# power_and_interface.net
KiCad netlist of a schematic drawn in Altium Designer
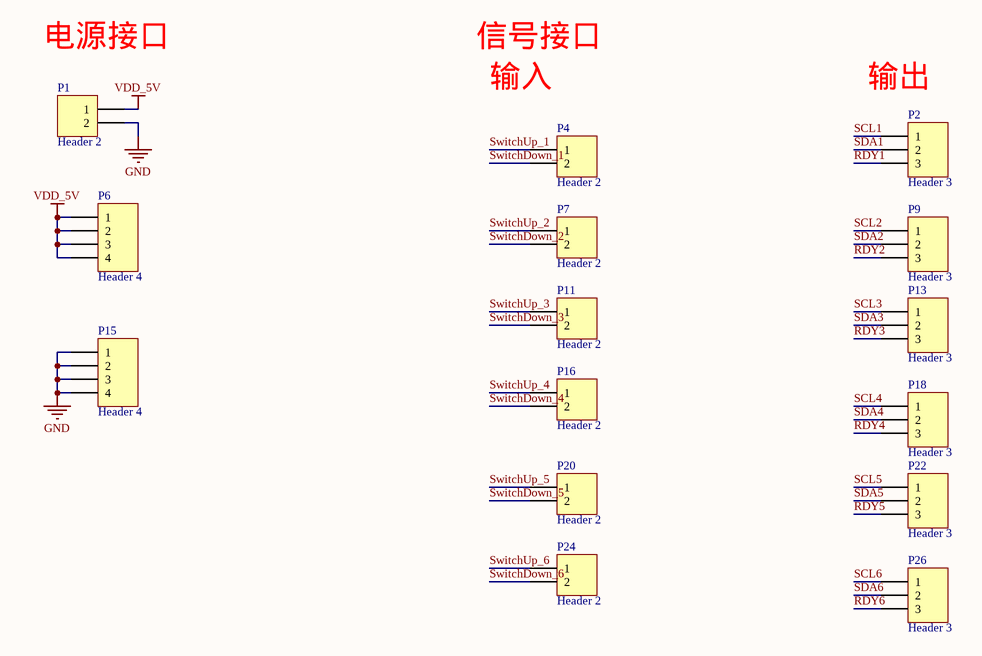
[diagram p0: power_and_interface.SchDoc]

(export (version "E")
  (design (tool "Eeschema 10.0.6"))
  (components
    (comp (ref "P1")
      (value "Header 2")
      (footprint "XH2.54-LI-2P")
      (description "Header, 2-Pin")
      (fields (field (name "PUBLISHER") "Altium Limited"))
      (libsource (lib "") (part "Header 2_1"))
    )
    (comp (ref "P2")
      (value "Header 3")
      (footprint "XH2.0_3p")
      (description "Header, 3-Pin")
      (fields (field (name "PUBLISHER") "Altium Limited"))
      (libsource (lib "Miscellaneous Connectors") (part "Header 3"))
    )
    (comp (ref "P4")
      (value "Header 2")
      (footprint "XH2.0_2p")
      (description "Header, 2-Pin")
      (fields (field (name "PUBLISHER") "Altium Limited"))
      (libsource (lib "Miscellaneous Connectors") (part "Header 2"))
    )
    (comp (ref "P6")
      (value "Header 4")
      (footprint "HDR1X4")
      (description "Header, 4-Pin")
      (fields (field (name "PUBLISHER") "Altium Limited"))
      (libsource (lib "YD-LibrarySCH") (part "Header 4"))
    )
    (comp (ref "P7")
      (value "Header 2")
      (footprint "XH2.0_2p")
      (description "Header, 2-Pin")
      (fields (field (name "PUBLISHER") "Altium Limited"))
      (libsource (lib "Miscellaneous Connectors") (part "Header 2"))
    )
    (comp (ref "P9")
      (value "Header 3")
      (footprint "XH2.0_3p")
      (description "Header, 3-Pin")
      (fields (field (name "PUBLISHER") "Altium Limited"))
      (libsource (lib "Miscellaneous Connectors") (part "Header 3"))
    )
    (comp (ref "P11")
      (value "Header 2")
      (footprint "XH2.0_2p")
      (description "Header, 2-Pin")
      (fields (field (name "PUBLISHER") "Altium Limited"))
      (libsource (lib "Miscellaneous Connectors") (part "Header 2"))
    )
    (comp (ref "P13")
      (value "Header 3")
      (footprint "XH2.0_3p")
      (description "Header, 3-Pin")
      (fields (field (name "PUBLISHER") "Altium Limited"))
      (libsource (lib "Miscellaneous Connectors") (part "Header 3"))
    )
    (comp (ref "P15")
      (value "Header 4")
      (footprint "HDR1X4")
      (description "Header, 4-Pin")
      (fields (field (name "PUBLISHER") "Altium Limited"))
      (libsource (lib "YD-LibrarySCH") (part "Header 4"))
    )
    (comp (ref "P16")
      (value "Header 2")
      (footprint "XH2.0_2p")
      (description "Header, 2-Pin")
      (fields (field (name "PUBLISHER") "Altium Limited"))
      (libsource (lib "Miscellaneous Connectors") (part "Header 2"))
    )
    (comp (ref "P18")
      (value "Header 3")
      (footprint "XH2.0_3p")
      (description "Header, 3-Pin")
      (fields (field (name "PUBLISHER") "Altium Limited"))
      (libsource (lib "Miscellaneous Connectors") (part "Header 3"))
    )
    (comp (ref "P20")
      (value "Header 2")
      (footprint "XH2.0_2p")
      (description "Header, 2-Pin")
      (fields (field (name "PUBLISHER") "Altium Limited"))
      (libsource (lib "Miscellaneous Connectors") (part "Header 2"))
    )
    (comp (ref "P22")
      (value "Header 3")
      (footprint "XH2.0_3p")
      (description "Header, 3-Pin")
      (fields (field (name "PUBLISHER") "Altium Limited"))
      (libsource (lib "Miscellaneous Connectors") (part "Header 3"))
    )
    (comp (ref "P24")
      (value "Header 2")
      (footprint "XH2.0_2p")
      (description "Header, 2-Pin")
      (fields (field (name "PUBLISHER") "Altium Limited"))
      (libsource (lib "Miscellaneous Connectors") (part "Header 2"))
    )
    (comp (ref "P26")
      (value "Header 3")
      (footprint "XH2.0_3p")
      (description "Header, 3-Pin")
      (fields (field (name "PUBLISHER") "Altium Limited"))
      (libsource (lib "Miscellaneous Connectors") (part "Header 3"))
    )
  )
  (nets
    (net (code "1") (name "/RDY1") (class "Default")
      (node (ref "P2") (pin "3") (pinfunction "3_3") (pintype "passive"))
    )
    (net (code "2") (name "/RDY2") (class "Default")
      (node (ref "P9") (pin "3") (pinfunction "3_3") (pintype "passive"))
    )
    (net (code "3") (name "/RDY3") (class "Default")
      (node (ref "P13") (pin "3") (pinfunction "3_3") (pintype "passive"))
    )
    (net (code "4") (name "/RDY4") (class "Default")
      (node (ref "P18") (pin "3") (pinfunction "3_3") (pintype "passive"))
    )
    (net (code "5") (name "/RDY5") (class "Default")
      (node (ref "P22") (pin "3") (pinfunction "3_3") (pintype "passive"))
    )
    (net (code "6") (name "/RDY6") (class "Default")
      (node (ref "P26") (pin "3") (pinfunction "3_3") (pintype "passive"))
    )
    (net (code "7") (name "/SCL1") (class "Default")
      (node (ref "P2") (pin "1") (pinfunction "1_1") (pintype "passive"))
    )
    (net (code "8") (name "/SCL2") (class "Default")
      (node (ref "P9") (pin "1") (pinfunction "1_1") (pintype "passive"))
    )
    (net (code "9") (name "/SCL3") (class "Default")
      (node (ref "P13") (pin "1") (pinfunction "1_1") (pintype "passive"))
    )
    (net (code "10") (name "/SCL4") (class "Default")
      (node (ref "P18") (pin "1") (pinfunction "1_1") (pintype "passive"))
    )
    (net (code "11") (name "/SCL5") (class "Default")
      (node (ref "P22") (pin "1") (pinfunction "1_1") (pintype "passive"))
    )
    (net (code "12") (name "/SCL6") (class "Default")
      (node (ref "P26") (pin "1") (pinfunction "1_1") (pintype "passive"))
    )
    (net (code "13") (name "/SDA1") (class "Default")
      (node (ref "P2") (pin "2") (pinfunction "2_2") (pintype "passive"))
    )
    (net (code "14") (name "/SDA2") (class "Default")
      (node (ref "P9") (pin "2") (pinfunction "2_2") (pintype "passive"))
    )
    (net (code "15") (name "/SDA3") (class "Default")
      (node (ref "P13") (pin "2") (pinfunction "2_2") (pintype "passive"))
    )
    (net (code "16") (name "/SDA4") (class "Default")
      (node (ref "P18") (pin "2") (pinfunction "2_2") (pintype "passive"))
    )
    (net (code "17") (name "/SDA5") (class "Default")
      (node (ref "P22") (pin "2") (pinfunction "2_2") (pintype "passive"))
    )
    (net (code "18") (name "/SDA6") (class "Default")
      (node (ref "P26") (pin "2") (pinfunction "2_2") (pintype "passive"))
    )
    (net (code "19") (name "/SwitchDown_1") (class "Default")
      (node (ref "P4") (pin "2") (pinfunction "2_2") (pintype "passive"))
    )
    (net (code "20") (name "/SwitchDown_2") (class "Default")
      (node (ref "P7") (pin "2") (pinfunction "2_2") (pintype "passive"))
    )
    (net (code "21") (name "/SwitchDown_3") (class "Default")
      (node (ref "P11") (pin "2") (pinfunction "2_2") (pintype "passive"))
    )
    (net (code "22") (name "/SwitchDown_4") (class "Default")
      (node (ref "P16") (pin "2") (pinfunction "2_2") (pintype "passive"))
    )
    (net (code "23") (name "/SwitchDown_5") (class "Default")
      (node (ref "P20") (pin "2") (pinfunction "2_2") (pintype "passive"))
    )
    (net (code "24") (name "/SwitchDown_6") (class "Default")
      (node (ref "P24") (pin "2") (pinfunction "2_2") (pintype "passive"))
    )
    (net (code "25") (name "/SwitchUp_1") (class "Default")
      (node (ref "P4") (pin "1") (pinfunction "1_1") (pintype "passive"))
    )
    (net (code "26") (name "/SwitchUp_2") (class "Default")
      (node (ref "P7") (pin "1") (pinfunction "1_1") (pintype "passive"))
    )
    (net (code "27") (name "/SwitchUp_3") (class "Default")
      (node (ref "P11") (pin "1") (pinfunction "1_1") (pintype "passive"))
    )
    (net (code "28") (name "/SwitchUp_4") (class "Default")
      (node (ref "P16") (pin "1") (pinfunction "1_1") (pintype "passive"))
    )
    (net (code "29") (name "/SwitchUp_5") (class "Default")
      (node (ref "P20") (pin "1") (pinfunction "1_1") (pintype "passive"))
    )
    (net (code "30") (name "/SwitchUp_6") (class "Default")
      (node (ref "P24") (pin "1") (pinfunction "1_1") (pintype "passive"))
    )
    (net (code "35") (name "GND") (class "Default")
      (node (ref "P1") (pin "2") (pinfunction "2_2") (pintype "passive"))
      (node (ref "P15") (pin "1") (pinfunction "1_1") (pintype "passive"))
      (node (ref "P15") (pin "2") (pinfunction "2_2") (pintype "passive"))
      (node (ref "P15") (pin "3") (pinfunction "3_3") (pintype "passive"))
      (node (ref "P15") (pin "4") (pinfunction "4_4") (pintype "passive"))
    )
    (net (code "36") (name "VDD_5V") (class "Default")
      (node (ref "P1") (pin "1") (pinfunction "1_1") (pintype "passive"))
      (node (ref "P6") (pin "1") (pinfunction "1_1") (pintype "passive"))
      (node (ref "P6") (pin "2") (pinfunction "2_2") (pintype "passive"))
      (node (ref "P6") (pin "3") (pinfunction "3_3") (pintype "passive"))
      (node (ref "P6") (pin "4") (pinfunction "4_4") (pintype "passive"))
    )
  )
)
